# ServoBot.net
KiCad netlist of a schematic drawn in Altium Designer
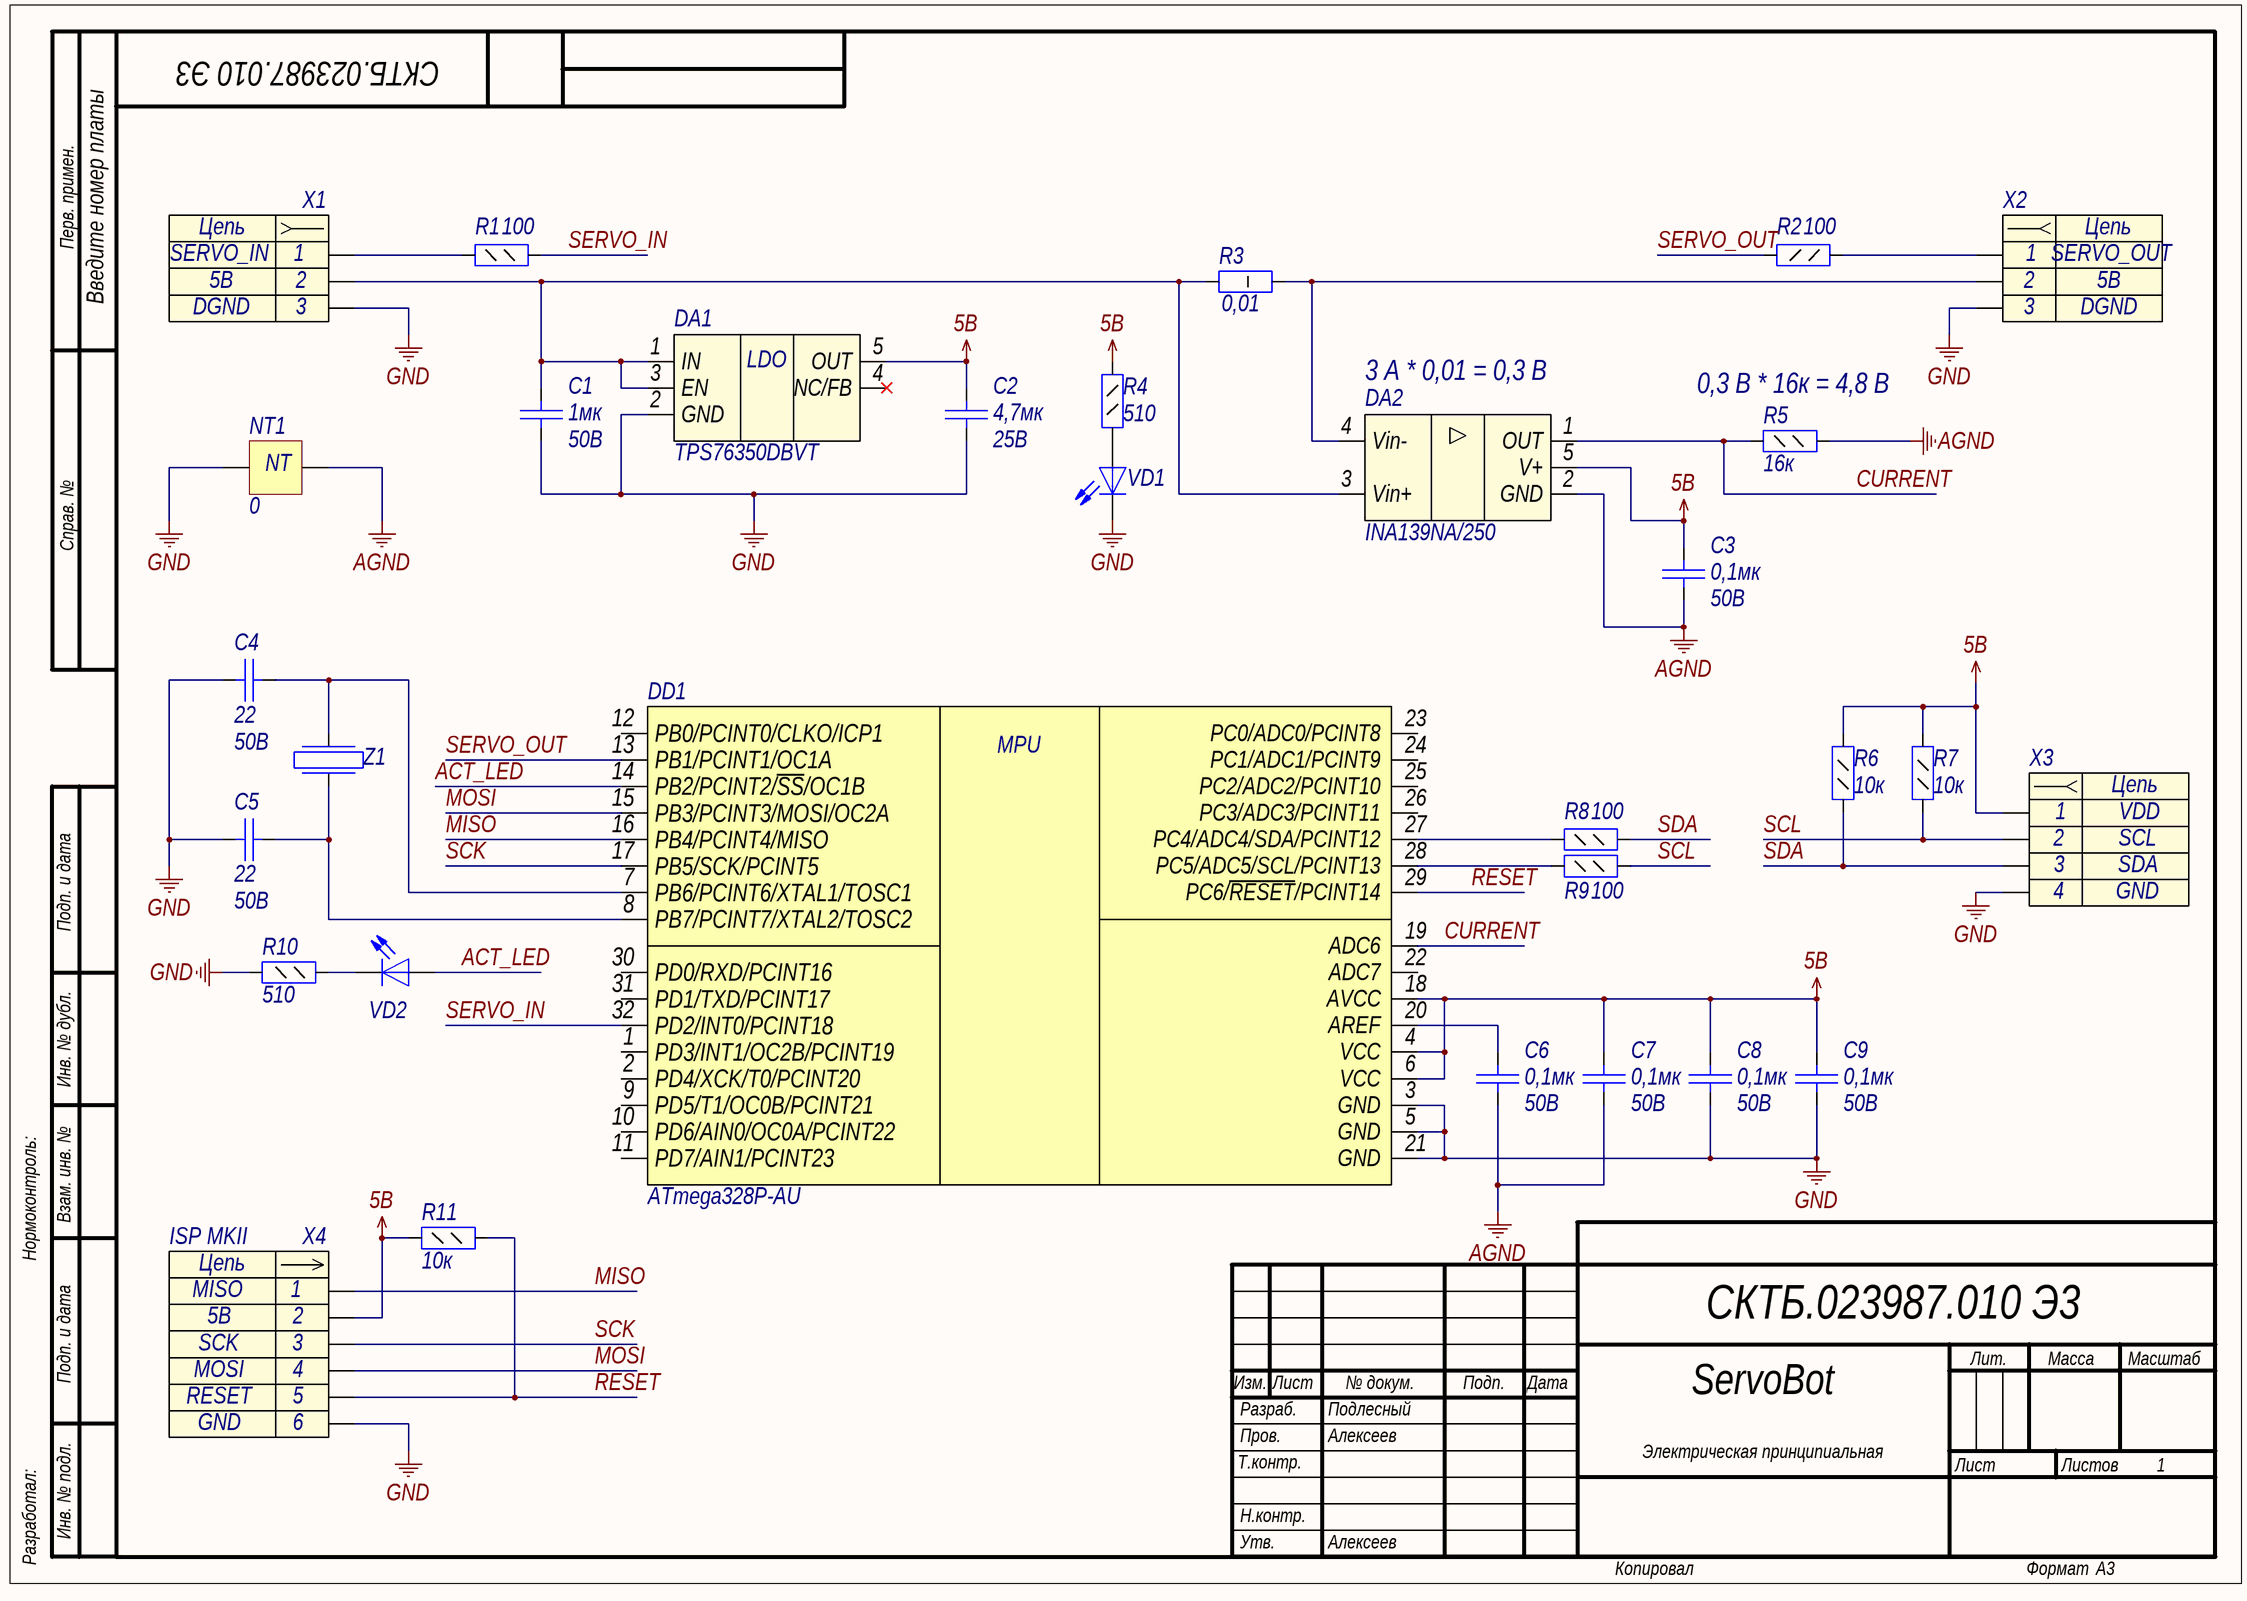
[diagram p0: ServoBot.SchDoc]

(export (version "E")
  (design (tool "Eeschema 10.0.6"))
  (components
    (comp (ref "C1")
      (value "1мк")
      (footprint "C0805")
      (description "Конденсатор")
      (fields (field (name "VOLTAGE") "50B") (field (name "PART NUMBER") "GRM21BR71H105K"))
      (libsource (lib "MOP44") (part "Capacitor"))
    )
    (comp (ref "C2")
      (value "4,7мк")
      (footprint "C0805")
      (description "Конденсатор")
      (fields (field (name "VOLTAGE") "25B") (field (name "PART NUMBER") "GRM21BR61E475KA12L"))
      (libsource (lib "MOP44") (part "Capacitor"))
    )
    (comp (ref "C3")
      (value "0,1мк")
      (footprint "C0805")
      (description "Конденсатор")
      (fields
        (field (name "VOLTAGE") "50B")
        (field (name "PART NUMBER") "GRM21BR71E225K")
        (field (name "Comment") "Capacitor")
      )
      (libsource (lib "MOP44") (part "Capacitor"))
    )
    (comp (ref "C4")
      (value "22")
      (footprint "C0805")
      (description "Конденсатор")
      (fields (field (name "VOLTAGE") "50В") (field (name "PART NUMBER") "GRM21A5C2E220JW01D"))
      (libsource (lib "MOP44") (part "Capacitor"))
    )
    (comp (ref "C5")
      (value "22")
      (footprint "C0805")
      (description "Конденсатор")
      (fields (field (name "VOLTAGE") "50В") (field (name "PART NUMBER") "GRM21A5C2E220JW01D"))
      (libsource (lib "MOP44") (part "Capacitor"))
    )
    (comp (ref "C6")
      (value "0,1мк")
      (footprint "C0805")
      (description "Конденсатор")
      (fields
        (field (name "VOLTAGE") "50В")
        (field (name "PART NUMBER") "GRM216R71H221K")
        (field (name "Comment") "Capacitor")
      )
      (libsource (lib "MOP44") (part "Capacitor"))
    )
    (comp (ref "C7")
      (value "0,1мк")
      (footprint "C0805")
      (description "Конденсатор")
      (fields
        (field (name "VOLTAGE") "50В")
        (field (name "PART NUMBER") "GRM216R71H221K")
        (field (name "Comment") "Capacitor")
      )
      (libsource (lib "MOP44") (part "Capacitor"))
    )
    (comp (ref "C8")
      (value "0,1мк")
      (footprint "C0805")
      (description "Конденсатор")
      (fields
        (field (name "VOLTAGE") "50В")
        (field (name "PART NUMBER") "GRM216R71H221K")
        (field (name "Comment") "Capacitor")
      )
      (libsource (lib "MOP44") (part "Capacitor"))
    )
    (comp (ref "C9")
      (value "0,1мк")
      (footprint "C0805")
      (description "Конденсатор")
      (fields
        (field (name "VOLTAGE") "50В")
        (field (name "PART NUMBER") "GRM216R71H221K")
        (field (name "Comment") "Capacitor")
      )
      (libsource (lib "MOP44") (part "Capacitor"))
    )
    (comp (ref "DA1")
      (value "TPS763x")
      (footprint "SOT23-5")
      (description "Low-Dropout Regulator")
      (fields (field (name "PART NUMBER") "TPS76350DBVT") (field (name "MANUFACTURER") "Texas Instruments"))
      (libsource (lib "MOP44") (part "TPS763x"))
    )
    (comp (ref "DA2")
      (value "INA1x9")
      (footprint "SOT23-5")
      (description "Измерительный датчик тока")
      (fields (field (name "PART NUMBER") "INA139NA/250"))
      (libsource (lib "MOP44") (part "INA1x9"))
    )
    (comp (ref "DD1")
      (value "ATmega328P-AU")
      (footprint "TQFP-32")
      (description "Микроконтроллер 8-Бит, picoPower, AVR, 20МГц, 32КБ Flash")
      (libsource (lib "MOP44") (part "ATmega328P-AU"))
    )
    (comp (ref "NT1")
      (value "0")
      (footprint "Pofigistor0603")
      (fields (field (name "Comment") "Pofigistor"))
      (libsource (lib "MOP44") (part "Pofigistor"))
    )
    (comp (ref "R1")
      (value "100")
      (footprint "R0805")
      (description "Резистор")
      (fields (field (name "PART NUMBER") "RC0805FR-07100RL") (field (name "POWER") "0,125Вт"))
      (libsource (lib "MOP44") (part "Resistor_0,125Вт"))
    )
    (comp (ref "R2")
      (value "100")
      (footprint "R0805")
      (description "Резистор")
      (fields (field (name "PART NUMBER") "RC0805FR-07100RL") (field (name "POWER") "0,125Вт"))
      (libsource (lib "") (part "Resistor_0,125Вт_2"))
    )
    (comp (ref "R3")
      (value "0,01")
      (footprint "R2512")
      (description "Резистор")
      (fields (field (name "PART NUMBER") "RC2512FR-070RL") (field (name "POWER") "1Вт"))
      (libsource (lib "MOP44") (part "Resistor_1Вт"))
    )
    (comp (ref "R4")
      (value "510")
      (footprint "R0805")
      (description "Резистор")
      (fields (field (name "PART NUMBER") "RC0805FR-07510RL") (field (name "POWER") "0,125Вт"))
      (libsource (lib "") (part "Resistor_0,125Вт_2"))
    )
    (comp (ref "R5")
      (value "16к")
      (footprint "R0805")
      (description "Резистор")
      (fields (field (name "PART NUMBER") "RC0805FR-0716KL") (field (name "POWER") "0,125Вт"))
      (libsource (lib "MOP44") (part "Resistor_0,125Вт"))
    )
    (comp (ref "R6")
      (value "10к")
      (footprint "R0805")
      (description "Резистор")
      (fields (field (name "PART NUMBER") "RC0805FR-0710KL") (field (name "POWER") "0,125Вт"))
      (libsource (lib "MOP44") (part "Resistor_0,125Вт"))
    )
    (comp (ref "R7")
      (value "10к")
      (footprint "R0805")
      (description "Резистор")
      (fields (field (name "PART NUMBER") "RC0805FR-0710KL") (field (name "POWER") "0,125Вт"))
      (libsource (lib "MOP44") (part "Resistor_0,125Вт"))
    )
    (comp (ref "R8")
      (value "100")
      (footprint "R0805")
      (description "Резистор")
      (fields (field (name "PART NUMBER") "RC0805FR-07100RL") (field (name "POWER") "0,125Вт"))
      (libsource (lib "MOP44") (part "Resistor_0,125Вт"))
    )
    (comp (ref "R9")
      (value "100")
      (footprint "R0805")
      (description "Резистор")
      (fields (field (name "PART NUMBER") "RC0805FR-07100RL") (field (name "POWER") "0,125Вт"))
      (libsource (lib "MOP44") (part "Resistor_0,125Вт"))
    )
    (comp (ref "R10")
      (value "510")
      (footprint "R0805")
      (description "Резистор")
      (fields (field (name "PART NUMBER") "RC0805FR-0710KL") (field (name "POWER") "0,125Вт"))
      (libsource (lib "") (part "Resistor_0,125Вт_1"))
    )
    (comp (ref "R11")
      (value "10к")
      (footprint "R0805")
      (description "Резистор")
      (fields (field (name "PART NUMBER") "RC0805FR-0710KL") (field (name "POWER") "0,125Вт"))
      (libsource (lib "MOP44") (part "Resistor_0,125Вт"))
    )
    (comp (ref "VD1")
      (value "LED")
      (footprint "L_0805")
      (description "Светодиод")
      (fields (field (name "PART NUMBER") "KP-2012EC"))
      (libsource (lib "MOP44") (part "LED"))
    )
    (comp (ref "VD2")
      (value "LED")
      (footprint "L_0805")
      (description "Светодиод")
      (fields (field (name "PART NUMBER") "KP-2012EC"))
      (libsource (lib "MOP44") (part "LED"))
    )
    (comp (ref "X1")
      (value "Header_3_sct")
      (footprint "PLS-3R")
      (description "Разъем - 3 конт. розетка")
      (fields (field (name "PART NUMBER") "DS1022-1*3RDF11-B"))
      (libsource (lib "") (part "Header_3_sct_1"))
    )
    (comp (ref "X2")
      (value "Header_3_sct")
      (footprint "PLS-3R")
      (description "Разъем - 3 конт. розетка")
      (fields (field (name "PART NUMBER") "DS1022-1*3RDF11-B"))
      (libsource (lib "MOP44") (part "Header_3_sct"))
    )
    (comp (ref "X3")
      (value "Header_4_sct")
      (footprint "PLS-4R")
      (description "Разъем - 4 конт. розетка")
      (fields (field (name "PART NUMBER") "DS1022-1*4RDF11-B"))
      (libsource (lib "MOP44") (part "Header_4_sct"))
    )
    (comp (ref "X4")
      (value "ISP MKII")
      (footprint "PLS2-6")
      (description "Разъем - 6 конт. вилка")
      (libsource (lib "MOP44") (part "ISP MKII"))
    )
    (comp (ref "Z1")
      (value "Crystal")
      (footprint "HC-49S")
      (description "Кварцевый резонатор")
      (fields (field (name "PART NUMBER") "16.000MHzHC-49US"))
      (libsource (lib "MOP44") (part "Crystal"))
    )
  )
  (nets
    (net (code "1") (name "/ACT_LED") (class "Default")
      (node (ref "DD1") (pin "14") (pinfunction "PB2/PCINT2/~{SS}/OC1B_14") (pintype "passive"))
      (node (ref "VD2") (pin "2") (pinfunction "A_2") (pintype "passive"))
    )
    (net (code "2") (name "/CURRENT") (class "Default")
      (node (ref "DA2") (pin "1") (pinfunction "OUT_1") (pintype "power_in"))
      (node (ref "DD1") (pin "19") (pinfunction "ADC6_19") (pintype "passive"))
      (node (ref "R5") (pin "1") (pinfunction "1_1") (pintype "passive"))
    )
    (net (code "3") (name "/MISO") (class "Default")
      (node (ref "DD1") (pin "16") (pinfunction "PB4/PCINT4/MISO_16") (pintype "passive"))
      (node (ref "X4") (pin "1") (pinfunction "1_1") (pintype "passive"))
    )
    (net (code "4") (name "/MOSI") (class "Default")
      (node (ref "DD1") (pin "15") (pinfunction "PB3/PCINT3/MOSI/OC2A_15") (pintype "passive"))
      (node (ref "X4") (pin "4") (pinfunction "4_4") (pintype "passive"))
    )
    (net (code "5") (name "/RESET") (class "Default")
      (node (ref "DD1") (pin "29") (pinfunction "PC6/~{RESET}/PCINT14_29") (pintype "passive"))
      (node (ref "R11") (pin "2") (pinfunction "2_2") (pintype "passive"))
      (node (ref "X4") (pin "5") (pinfunction "5_5") (pintype "passive"))
    )
    (net (code "6") (name "/SCK") (class "Default")
      (node (ref "DD1") (pin "17") (pinfunction "PB5/SCK/PCINT5_17") (pintype "passive"))
      (node (ref "X4") (pin "3") (pinfunction "3_3") (pintype "passive"))
    )
    (net (code "7") (name "/SCL") (class "Default")
      (node (ref "R7") (pin "1") (pinfunction "1_1") (pintype "passive"))
      (node (ref "R9") (pin "2") (pinfunction "2_2") (pintype "passive"))
      (node (ref "X3") (pin "2") (pinfunction "2_2") (pintype "passive"))
    )
    (net (code "8") (name "/SDA") (class "Default")
      (node (ref "R6") (pin "1") (pinfunction "1_1") (pintype "passive"))
      (node (ref "R8") (pin "2") (pinfunction "2_2") (pintype "passive"))
      (node (ref "X3") (pin "3") (pinfunction "3_3") (pintype "passive"))
    )
    (net (code "9") (name "/SERVO_IN") (class "Default")
      (node (ref "DD1") (pin "32") (pinfunction "PD2/INT0/PCINT18_32") (pintype "passive"))
      (node (ref "R1") (pin "2") (pinfunction "2_2") (pintype "passive"))
    )
    (net (code "10") (name "/SERVO_OUT") (class "Default")
      (node (ref "DD1") (pin "13") (pinfunction "PB1/PCINT1/OC1A_13") (pintype "passive"))
      (node (ref "R2") (pin "2") (pinfunction "2_2") (pintype "passive"))
    )
    (net (code "11") (name "5B") (class "Default")
      (node (ref "C2") (pin "2") (pinfunction "2_2") (pintype "passive"))
      (node (ref "C3") (pin "2") (pinfunction "2_2") (pintype "passive"))
      (node (ref "C7") (pin "1") (pinfunction "1_1") (pintype "passive"))
      (node (ref "C8") (pin "1") (pinfunction "1_1") (pintype "passive"))
      (node (ref "C9") (pin "1") (pinfunction "1_1") (pintype "passive"))
      (node (ref "DA1") (pin "5") (pinfunction "OUT_5") (pintype "power_in"))
      (node (ref "DA2") (pin "5") (pinfunction "V+_5") (pintype "power_in"))
      (node (ref "DD1") (pin "18") (pinfunction "AVCC_18") (pintype "passive"))
      (node (ref "DD1") (pin "4") (pinfunction "VCC_4") (pintype "passive"))
      (node (ref "DD1") (pin "6") (pinfunction "VCC_6") (pintype "passive"))
      (node (ref "R11") (pin "1") (pinfunction "1_1") (pintype "passive"))
      (node (ref "R4") (pin "1") (pinfunction "1_1") (pintype "passive"))
      (node (ref "R6") (pin "2") (pinfunction "2_2") (pintype "passive"))
      (node (ref "R7") (pin "2") (pinfunction "2_2") (pintype "passive"))
      (node (ref "X3") (pin "1") (pinfunction "1_1") (pintype "passive"))
      (node (ref "X4") (pin "2") (pinfunction "2_2") (pintype "passive"))
    )
    (net (code "12") (name "AGND") (class "Default")
      (node (ref "C3") (pin "1") (pinfunction "1_1") (pintype "passive"))
      (node (ref "C6") (pin "2") (pinfunction "2_2") (pintype "passive"))
      (node (ref "C7") (pin "2") (pinfunction "2_2") (pintype "passive"))
      (node (ref "DA2") (pin "2") (pinfunction "GND_2") (pintype "power_in"))
      (node (ref "NT1") (pin "2") (pinfunction "2_2") (pintype "passive"))
      (node (ref "R5") (pin "2") (pinfunction "2_2") (pintype "passive"))
    )
    (net (code "13") (name "GND") (class "Default")
      (node (ref "C1") (pin "1") (pinfunction "1_1") (pintype "passive"))
      (node (ref "C2") (pin "1") (pinfunction "1_1") (pintype "passive"))
      (node (ref "C4") (pin "1") (pinfunction "1_1") (pintype "passive"))
      (node (ref "C5") (pin "1") (pinfunction "1_1") (pintype "passive"))
      (node (ref "C8") (pin "2") (pinfunction "2_2") (pintype "passive"))
      (node (ref "C9") (pin "2") (pinfunction "2_2") (pintype "passive"))
      (node (ref "DA1") (pin "2") (pinfunction "GND_2") (pintype "power_in"))
      (node (ref "DD1") (pin "21") (pinfunction "GND_21") (pintype "passive"))
      (node (ref "DD1") (pin "3") (pinfunction "GND_3") (pintype "passive"))
      (node (ref "DD1") (pin "5") (pinfunction "GND_5") (pintype "passive"))
      (node (ref "NT1") (pin "1") (pinfunction "1_1") (pintype "passive"))
      (node (ref "R10") (pin "2") (pinfunction "2_2") (pintype "passive"))
      (node (ref "VD1") (pin "1") (pinfunction "K_1") (pintype "passive"))
      (node (ref "X1") (pin "3") (pinfunction "3_3") (pintype "passive"))
      (node (ref "X2") (pin "3") (pinfunction "3_3") (pintype "passive"))
      (node (ref "X3") (pin "4") (pinfunction "4_4") (pintype "passive"))
      (node (ref "X4") (pin "6") (pinfunction "6_6") (pintype "passive"))
    )
    (net (code "14") (name "Net-(DA1-EN)") (class "Default")
      (node (ref "C1") (pin "2") (pinfunction "2_2") (pintype "passive"))
      (node (ref "DA1") (pin "1") (pinfunction "IN_1") (pintype "power_in"))
      (node (ref "DA1") (pin "3") (pinfunction "EN_3") (pintype "power_in"))
      (node (ref "DA2") (pin "3") (pinfunction "Vin+_3") (pintype "power_in"))
      (node (ref "R3") (pin "1") (pinfunction "1_1") (pintype "passive"))
      (node (ref "X1") (pin "2") (pinfunction "2_2") (pintype "passive"))
    )
    (net (code "15") (name "Net-(DA2-Vin-)") (class "Default")
      (node (ref "DA2") (pin "4") (pinfunction "Vin-_4") (pintype "power_in"))
      (node (ref "R3") (pin "2") (pinfunction "5_2") (pintype "passive"))
      (node (ref "X2") (pin "2") (pinfunction "2_2") (pintype "passive"))
    )
    (net (code "16") (name "Net-(DD1-AREF)") (class "Default")
      (node (ref "C6") (pin "1") (pinfunction "1_1") (pintype "passive"))
      (node (ref "DD1") (pin "20") (pinfunction "AREF_20") (pintype "passive"))
    )
    (net (code "17") (name "Net-(DD1-PB6{slash}PCINT6{slash}XTAL1{slash}TOSC1)") (class "Default")
      (node (ref "C4") (pin "2") (pinfunction "2_2") (pintype "passive"))
      (node (ref "DD1") (pin "7") (pinfunction "PB6/PCINT6/XTAL1/TOSC1_7") (pintype "passive"))
      (node (ref "Z1") (pin "2") (pinfunction "2_2") (pintype "passive"))
    )
    (net (code "18") (name "Net-(DD1-PB7{slash}PCINT7{slash}XTAL2{slash}TOSC2)") (class "Default")
      (node (ref "C5") (pin "2") (pinfunction "2_2") (pintype "passive"))
      (node (ref "DD1") (pin "8") (pinfunction "PB7/PCINT7/XTAL2/TOSC2_8") (pintype "passive"))
      (node (ref "Z1") (pin "1") (pinfunction "1_1") (pintype "passive"))
    )
    (net (code "19") (name "Net-(DD1-PC4{slash}ADC4{slash}SDA{slash}PCINT12)") (class "Default")
      (node (ref "DD1") (pin "27") (pinfunction "PC4/ADC4/SDA/PCINT12_27") (pintype "passive"))
      (node (ref "R8") (pin "1") (pinfunction "1_1") (pintype "passive"))
    )
    (net (code "20") (name "Net-(DD1-PC5{slash}ADC5{slash}SCL{slash}PCINT13)") (class "Default")
      (node (ref "DD1") (pin "28") (pinfunction "PC5/ADC5/SCL/PCINT13_28") (pintype "passive"))
      (node (ref "R9") (pin "1") (pinfunction "1_1") (pintype "passive"))
    )
    (net (code "21") (name "Net-(R1-Pad1)") (class "Default")
      (node (ref "R1") (pin "1") (pinfunction "1_1") (pintype "passive"))
      (node (ref "X1") (pin "1") (pinfunction "1_1") (pintype "passive"))
    )
    (net (code "22") (name "Net-(R2-Pad1)") (class "Default")
      (node (ref "R2") (pin "1") (pinfunction "1_1") (pintype "passive"))
      (node (ref "X2") (pin "1") (pinfunction "1_1") (pintype "passive"))
    )
    (net (code "23") (name "Net-(VD1-A)") (class "Default")
      (node (ref "R4") (pin "2") (pinfunction "2_2") (pintype "passive"))
      (node (ref "VD1") (pin "2") (pinfunction "A_2") (pintype "passive"))
    )
    (net (code "24") (name "Net-(VD2-K)") (class "Default")
      (node (ref "R10") (pin "1") (pinfunction "1_1") (pintype "passive"))
      (node (ref "VD2") (pin "1") (pinfunction "K_1") (pintype "passive"))
    )
    (net (code "25") (name "unconnected-(DA1-NC{slash}FB-Pad4)") (class "Default")
      (node (ref "DA1") (pin "4") (pinfunction "NC/FB_4") (pintype "power_in+no_connect"))
    )
    (net (code "26") (name "unconnected-(DD1-ADC7-Pad22)") (class "Default")
      (node (ref "DD1") (pin "22") (pinfunction "ADC7_22") (pintype "passive"))
    )
    (net (code "27") (name "unconnected-(DD1-PB0{slash}PCINT0{slash}CLKO{slash}ICP1-Pad12)") (class "Default")
      (node (ref "DD1") (pin "12") (pinfunction "PB0/PCINT0/CLKO/ICP1_12") (pintype "passive"))
    )
    (net (code "28") (name "unconnected-(DD1-PC0{slash}ADC0{slash}PCINT8-Pad23)") (class "Default")
      (node (ref "DD1") (pin "23") (pinfunction "PC0/ADC0/PCINT8_23") (pintype "passive"))
    )
    (net (code "29") (name "unconnected-(DD1-PC1{slash}ADC1{slash}PCINT9-Pad24)") (class "Default")
      (node (ref "DD1") (pin "24") (pinfunction "PC1/ADC1/PCINT9_24") (pintype "passive"))
    )
    (net (code "30") (name "unconnected-(DD1-PC2{slash}ADC2{slash}PCINT10-Pad25)") (class "Default")
      (node (ref "DD1") (pin "25") (pinfunction "PC2/ADC2/PCINT10_25") (pintype "passive"))
    )
    (net (code "31") (name "unconnected-(DD1-PC3{slash}ADC3{slash}PCINT11-Pad26)") (class "Default")
      (node (ref "DD1") (pin "26") (pinfunction "PC3/ADC3/PCINT11_26") (pintype "passive"))
    )
    (net (code "32") (name "unconnected-(DD1-PD0{slash}RXD{slash}PCINT16-Pad30)") (class "Default")
      (node (ref "DD1") (pin "30") (pinfunction "PD0/RXD/PCINT16_30") (pintype "passive"))
    )
    (net (code "33") (name "unconnected-(DD1-PD1{slash}TXD{slash}PCINT17-Pad31)") (class "Default")
      (node (ref "DD1") (pin "31") (pinfunction "PD1/TXD/PCINT17_31") (pintype "passive"))
    )
    (net (code "34") (name "unconnected-(DD1-PD3{slash}INT1{slash}OC2B{slash}PCINT19-Pad1)") (class "Default")
      (node (ref "DD1") (pin "1") (pinfunction "PD3/INT1/OC2B/PCINT19_1") (pintype "passive"))
    )
    (net (code "35") (name "unconnected-(DD1-PD4{slash}XCK{slash}T0{slash}PCINT20-Pad2)") (class "Default")
      (node (ref "DD1") (pin "2") (pinfunction "PD4/XCK/T0/PCINT20_2") (pintype "passive"))
    )
    (net (code "36") (name "unconnected-(DD1-PD5{slash}T1{slash}OC0B{slash}PCINT21-Pad9)") (class "Default")
      (node (ref "DD1") (pin "9") (pinfunction "PD5/T1/OC0B/PCINT21_9") (pintype "passive"))
    )
    (net (code "37") (name "unconnected-(DD1-PD6{slash}AIN0{slash}OC0A{slash}PCINT22-Pad10)") (class "Default")
      (node (ref "DD1") (pin "10") (pinfunction "PD6/AIN0/OC0A/PCINT22_10") (pintype "passive"))
    )
    (net (code "38") (name "unconnected-(DD1-PD7{slash}AIN1{slash}PCINT23-Pad11)") (class "Default")
      (node (ref "DD1") (pin "11") (pinfunction "PD7/AIN1/PCINT23_11") (pintype "passive"))
    )
  )
)
